# contactor_feedback.net
KiCad netlist of a schematic drawn in Altium Designer
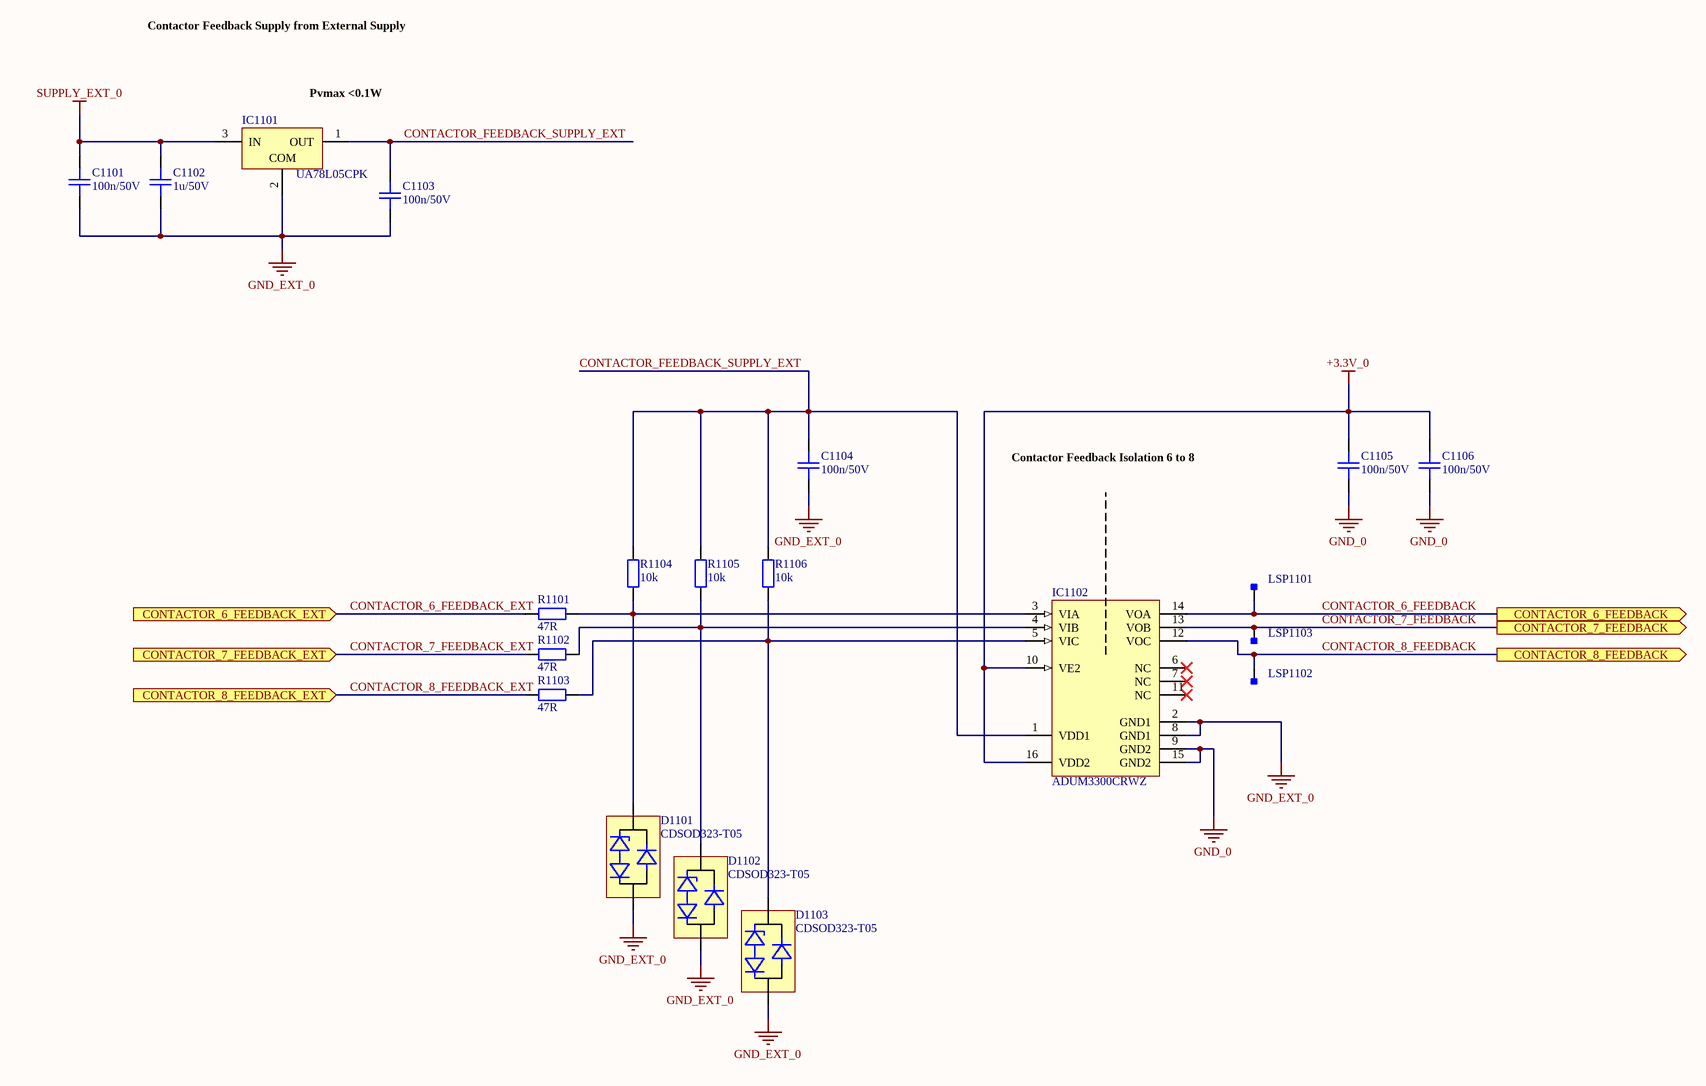
[diagram p0: contactor_feedback.SchDoc]

(export (version "E")
  (design (tool "Eeschema 10.0.6"))
  (components
    (comp (ref "C1101")
      (value "100n/50V")
      (footprint "CAPC1608X08N")
      (description "MLCC")
      (fields (field (name "PART NUMBER") "gen_C_ceramic_100n_50V_X7R_0603"))
      (libsource (lib "OE750") (part "C"))
    )
    (comp (ref "C1102")
      (value "1u/50V")
      (footprint "CAPC1608X08N")
      (description "MLCC")
      (fields (field (name "PART NUMBER") "gen_C_ceramic_1u_50V_X7R_0603") (field (name "TOLERANCE") "± 10%"))
      (libsource (lib "OE750") (part "C"))
    )
    (comp (ref "C1103")
      (value "100n/50V")
      (footprint "CAPC1608X08N")
      (description "MLCC")
      (fields (field (name "PART NUMBER") "gen_C_ceramic_100n_50V_X7R_0603"))
      (libsource (lib "OE750") (part "C"))
    )
    (comp (ref "C1104")
      (value "100n/50V")
      (footprint "CAPC1608X08N")
      (description "MLCC")
      (fields (field (name "PART NUMBER") "gen_C_ceramic_100n_50V_X7R_0603"))
      (libsource (lib "OE750") (part "C"))
    )
    (comp (ref "C1105")
      (value "100n/50V")
      (footprint "CAPC1608X08N")
      (description "MLCC")
      (fields (field (name "PART NUMBER") "gen_C_ceramic_100n_50V_X7R_0603"))
      (libsource (lib "OE750") (part "C"))
    )
    (comp (ref "C1106")
      (value "100n/50V")
      (footprint "CAPC1608X08N")
      (description "MLCC")
      (fields (field (name "PART NUMBER") "gen_C_ceramic_100n_50V_X7R_0603"))
      (libsource (lib "OE750") (part "C"))
    )
    (comp (ref "D1101")
      (value "CDSOD323-T05")
      (footprint "SODFL250X110-2N")
      (description "TVS Diode, CDSOD323 Series, Unidirectional, 5 V, 18.3 V, SOD-323, 2 Pins")
      (fields (field (name "MANUFACTURER") "Bourns"))
      (libsource (lib "OE750") (part "D_TVS_uni"))
    )
    (comp (ref "D1102")
      (value "CDSOD323-T05")
      (footprint "SODFL250X110-2N")
      (description "TVS Diode, CDSOD323 Series, Unidirectional, 5 V, 18.3 V, SOD-323, 2 Pins")
      (fields (field (name "MANUFACTURER") "Bourns"))
      (libsource (lib "OE750") (part "D_TVS_uni"))
    )
    (comp (ref "D1103")
      (value "CDSOD323-T05")
      (footprint "SODFL250X110-2N")
      (description "TVS Diode, CDSOD323 Series, Unidirectional, 5 V, 18.3 V, SOD-323, 2 Pins")
      (fields (field (name "MANUFACTURER") "Bourns"))
      (libsource (lib "OE750") (part "D_TVS_uni"))
    )
    (comp (ref "IC1101")
      (value "UA78L05CPK")
      (footprint "PK0003A_L")
      (fields (field (name "MANUFACTURER") "TexasInstruments"))
      (libsource (lib "Altium Content Vault") (part "TI-UA78L05-PK-3"))
    )
    (comp (ref "IC1102")
      (value "ADUM3300CRWZ")
      (footprint "ADI-RW-16_L")
      (fields (field (name "MANUFACTURER") "Analog Devices"))
      (libsource (lib "Altium Content Vault") (part "ADI-ADUMX300-RW-16"))
    )
    (comp (ref "LSP1101")
      (value "Testpoint_Square")
      (footprint "Testpoint_S1")
      (description "Testpoint, square")
      (libsource (lib "OE750") (part "Testpoint_Square"))
    )
    (comp (ref "LSP1102")
      (value "Testpoint_Square")
      (footprint "Testpoint_S1")
      (description "Testpoint, square")
      (libsource (lib "OE750") (part "Testpoint_Square"))
    )
    (comp (ref "LSP1103")
      (value "Testpoint_Square")
      (footprint "Testpoint_S1")
      (description "Testpoint, square")
      (libsource (lib "OE750") (part "Testpoint_Square"))
    )
    (comp (ref "R1101")
      (value "47R")
      (footprint "RESC1608X05N")
      (description "SMD Resistor 47R 0603")
      (fields (field (name "PART NUMBER") "gen_R_47R_0603") (field (name "TOLERANCE") "1%"))
      (libsource (lib "OE750") (part "R"))
    )
    (comp (ref "R1102")
      (value "47R")
      (footprint "RESC1608X05N")
      (description "SMD Resistor 47R 0603")
      (fields (field (name "PART NUMBER") "gen_R_47R_0603") (field (name "TOLERANCE") "1%"))
      (libsource (lib "OE750") (part "R"))
    )
    (comp (ref "R1103")
      (value "47R")
      (footprint "RESC1608X05N")
      (description "SMD Resistor 47R 0603")
      (fields (field (name "PART NUMBER") "gen_R_47R_0603") (field (name "TOLERANCE") "1%"))
      (libsource (lib "OE750") (part "R"))
    )
    (comp (ref "R1104")
      (value "10k")
      (footprint "RESC1608X05N")
      (description "SMD Resistor 10k 0603")
      (fields (field (name "PART NUMBER") "gen_R_10k_0603") (field (name "TOLERANCE") "1%"))
      (libsource (lib "OE750") (part "R"))
    )
    (comp (ref "R1105")
      (value "10k")
      (footprint "RESC1608X05N")
      (description "SMD Resistor 10k 0603")
      (fields (field (name "PART NUMBER") "gen_R_10k_0603") (field (name "TOLERANCE") "1%"))
      (libsource (lib "OE750") (part "R"))
    )
    (comp (ref "R1106")
      (value "10k")
      (footprint "RESC1608X05N")
      (description "SMD Resistor 10k 0603")
      (fields (field (name "PART NUMBER") "gen_R_10k_0603") (field (name "TOLERANCE") "1%"))
      (libsource (lib "OE750") (part "R"))
    )
  )
  (nets
    (net (code "1") (name "+3.3V_0") (class "Default")
      (node (ref "C1105") (pin "1") (pinfunction "1_1") (pintype "passive"))
      (node (ref "C1106") (pin "1") (pinfunction "1_1") (pintype "passive"))
      (node (ref "IC1102") (pin "10") (pinfunction "VE2_10") (pintype "input"))
      (node (ref "IC1102") (pin "16") (pinfunction "VDD2_16") (pintype "power_in"))
    )
    (net (code "2") (name "/CONTACTOR_6_FEEDBACK") (class "Default")
      (node (ref "IC1102") (pin "14") (pinfunction "VOA_14") (pintype "tri_state"))
      (node (ref "LSP1101") (pin "1") (pinfunction "1_1") (pintype "passive"))
    )
    (net (code "3") (name "/CONTACTOR_6_FEEDBACK_EXT") (class "Default")
      (node (ref "R1101") (pin "2") (pinfunction "2_2") (pintype "passive"))
    )
    (net (code "4") (name "/CONTACTOR_7_FEEDBACK") (class "Default")
      (node (ref "IC1102") (pin "13") (pinfunction "VOB_13") (pintype "tri_state"))
      (node (ref "LSP1103") (pin "1") (pinfunction "1_1") (pintype "passive"))
    )
    (net (code "5") (name "/CONTACTOR_7_FEEDBACK_EXT") (class "Default")
      (node (ref "R1102") (pin "2") (pinfunction "2_2") (pintype "passive"))
    )
    (net (code "6") (name "/CONTACTOR_8_FEEDBACK") (class "Default")
      (node (ref "IC1102") (pin "12") (pinfunction "VOC_12") (pintype "tri_state"))
      (node (ref "LSP1102") (pin "1") (pinfunction "1_1") (pintype "passive"))
    )
    (net (code "7") (name "/CONTACTOR_8_FEEDBACK_EXT") (class "Default")
      (node (ref "R1103") (pin "2") (pinfunction "2_2") (pintype "passive"))
    )
    (net (code "8") (name "/CONTACTOR_FEEDBACK_SUPPLY_EXT") (class "Default")
      (node (ref "C1103") (pin "1") (pinfunction "1_1") (pintype "passive"))
      (node (ref "C1104") (pin "1") (pinfunction "1_1") (pintype "passive"))
      (node (ref "IC1101") (pin "1") (pinfunction "OUT_1") (pintype "power_in"))
      (node (ref "IC1102") (pin "1") (pinfunction "VDD1_1") (pintype "power_in"))
      (node (ref "R1104") (pin "2") (pinfunction "2_2") (pintype "passive"))
      (node (ref "R1105") (pin "2") (pinfunction "2_2") (pintype "passive"))
      (node (ref "R1106") (pin "2") (pinfunction "2_2") (pintype "passive"))
    )
    (net (code "9") (name "GND_0") (class "Default")
      (node (ref "C1105") (pin "2") (pinfunction "2_2") (pintype "passive"))
      (node (ref "C1106") (pin "2") (pinfunction "2_2") (pintype "passive"))
      (node (ref "IC1102") (pin "15") (pinfunction "GND2_15") (pintype "power_in"))
      (node (ref "IC1102") (pin "9") (pinfunction "GND2_9") (pintype "power_in"))
    )
    (net (code "10") (name "GND_EXT_0") (class "Default")
      (node (ref "C1101") (pin "2") (pinfunction "2_2") (pintype "passive"))
      (node (ref "C1102") (pin "2") (pinfunction "2_2") (pintype "passive"))
      (node (ref "C1103") (pin "2") (pinfunction "2_2") (pintype "passive"))
      (node (ref "C1104") (pin "2") (pinfunction "2_2") (pintype "passive"))
      (node (ref "D1101") (pin "2") (pinfunction "A_2") (pintype "passive"))
      (node (ref "D1102") (pin "2") (pinfunction "A_2") (pintype "passive"))
      (node (ref "D1103") (pin "2") (pinfunction "A_2") (pintype "passive"))
      (node (ref "IC1101") (pin "2") (pinfunction "COM_2") (pintype "power_in"))
      (node (ref "IC1102") (pin "2") (pinfunction "GND1_2") (pintype "power_in"))
      (node (ref "IC1102") (pin "8") (pinfunction "GND1_8") (pintype "power_in"))
    )
    (net (code "11") (name "Net-(D1101-K)") (class "Default")
      (node (ref "D1101") (pin "1") (pinfunction "K_1") (pintype "passive"))
      (node (ref "IC1102") (pin "3") (pinfunction "VIA_3") (pintype "input"))
      (node (ref "R1101") (pin "1") (pinfunction "1_1") (pintype "passive"))
      (node (ref "R1104") (pin "1") (pinfunction "1_1") (pintype "passive"))
    )
    (net (code "12") (name "Net-(D1102-K)") (class "Default")
      (node (ref "D1102") (pin "1") (pinfunction "K_1") (pintype "passive"))
      (node (ref "IC1102") (pin "4") (pinfunction "VIB_4") (pintype "input"))
      (node (ref "R1102") (pin "1") (pinfunction "1_1") (pintype "passive"))
      (node (ref "R1105") (pin "1") (pinfunction "1_1") (pintype "passive"))
    )
    (net (code "13") (name "Net-(D1103-K)") (class "Default")
      (node (ref "D1103") (pin "1") (pinfunction "K_1") (pintype "passive"))
      (node (ref "IC1102") (pin "5") (pinfunction "VIC_5") (pintype "input"))
      (node (ref "R1103") (pin "1") (pinfunction "1_1") (pintype "passive"))
      (node (ref "R1106") (pin "1") (pinfunction "1_1") (pintype "passive"))
    )
    (net (code "14") (name "SUPPLY_EXT_0") (class "Default")
      (node (ref "C1101") (pin "1") (pinfunction "1_1") (pintype "passive"))
      (node (ref "C1102") (pin "1") (pinfunction "1_1") (pintype "passive"))
      (node (ref "IC1101") (pin "3") (pinfunction "IN_3") (pintype "power_in"))
    )
    (net (code "15") (name "unconnected-(IC1102-NC-Pad6)") (class "Default")
      (node (ref "IC1102") (pin "6") (pinfunction "NC_6") (pintype "passive+no_connect"))
    )
    (net (code "16") (name "unconnected-(IC1102-NC-Pad7)") (class "Default")
      (node (ref "IC1102") (pin "7") (pinfunction "NC_7") (pintype "passive+no_connect"))
    )
    (net (code "17") (name "unconnected-(IC1102-NC-Pad11)") (class "Default")
      (node (ref "IC1102") (pin "11") (pinfunction "NC_11") (pintype "passive+no_connect"))
    )
  )
)
